# PET_1541_Ada.net
KiCad netlist of a schematic drawn in EAGLE
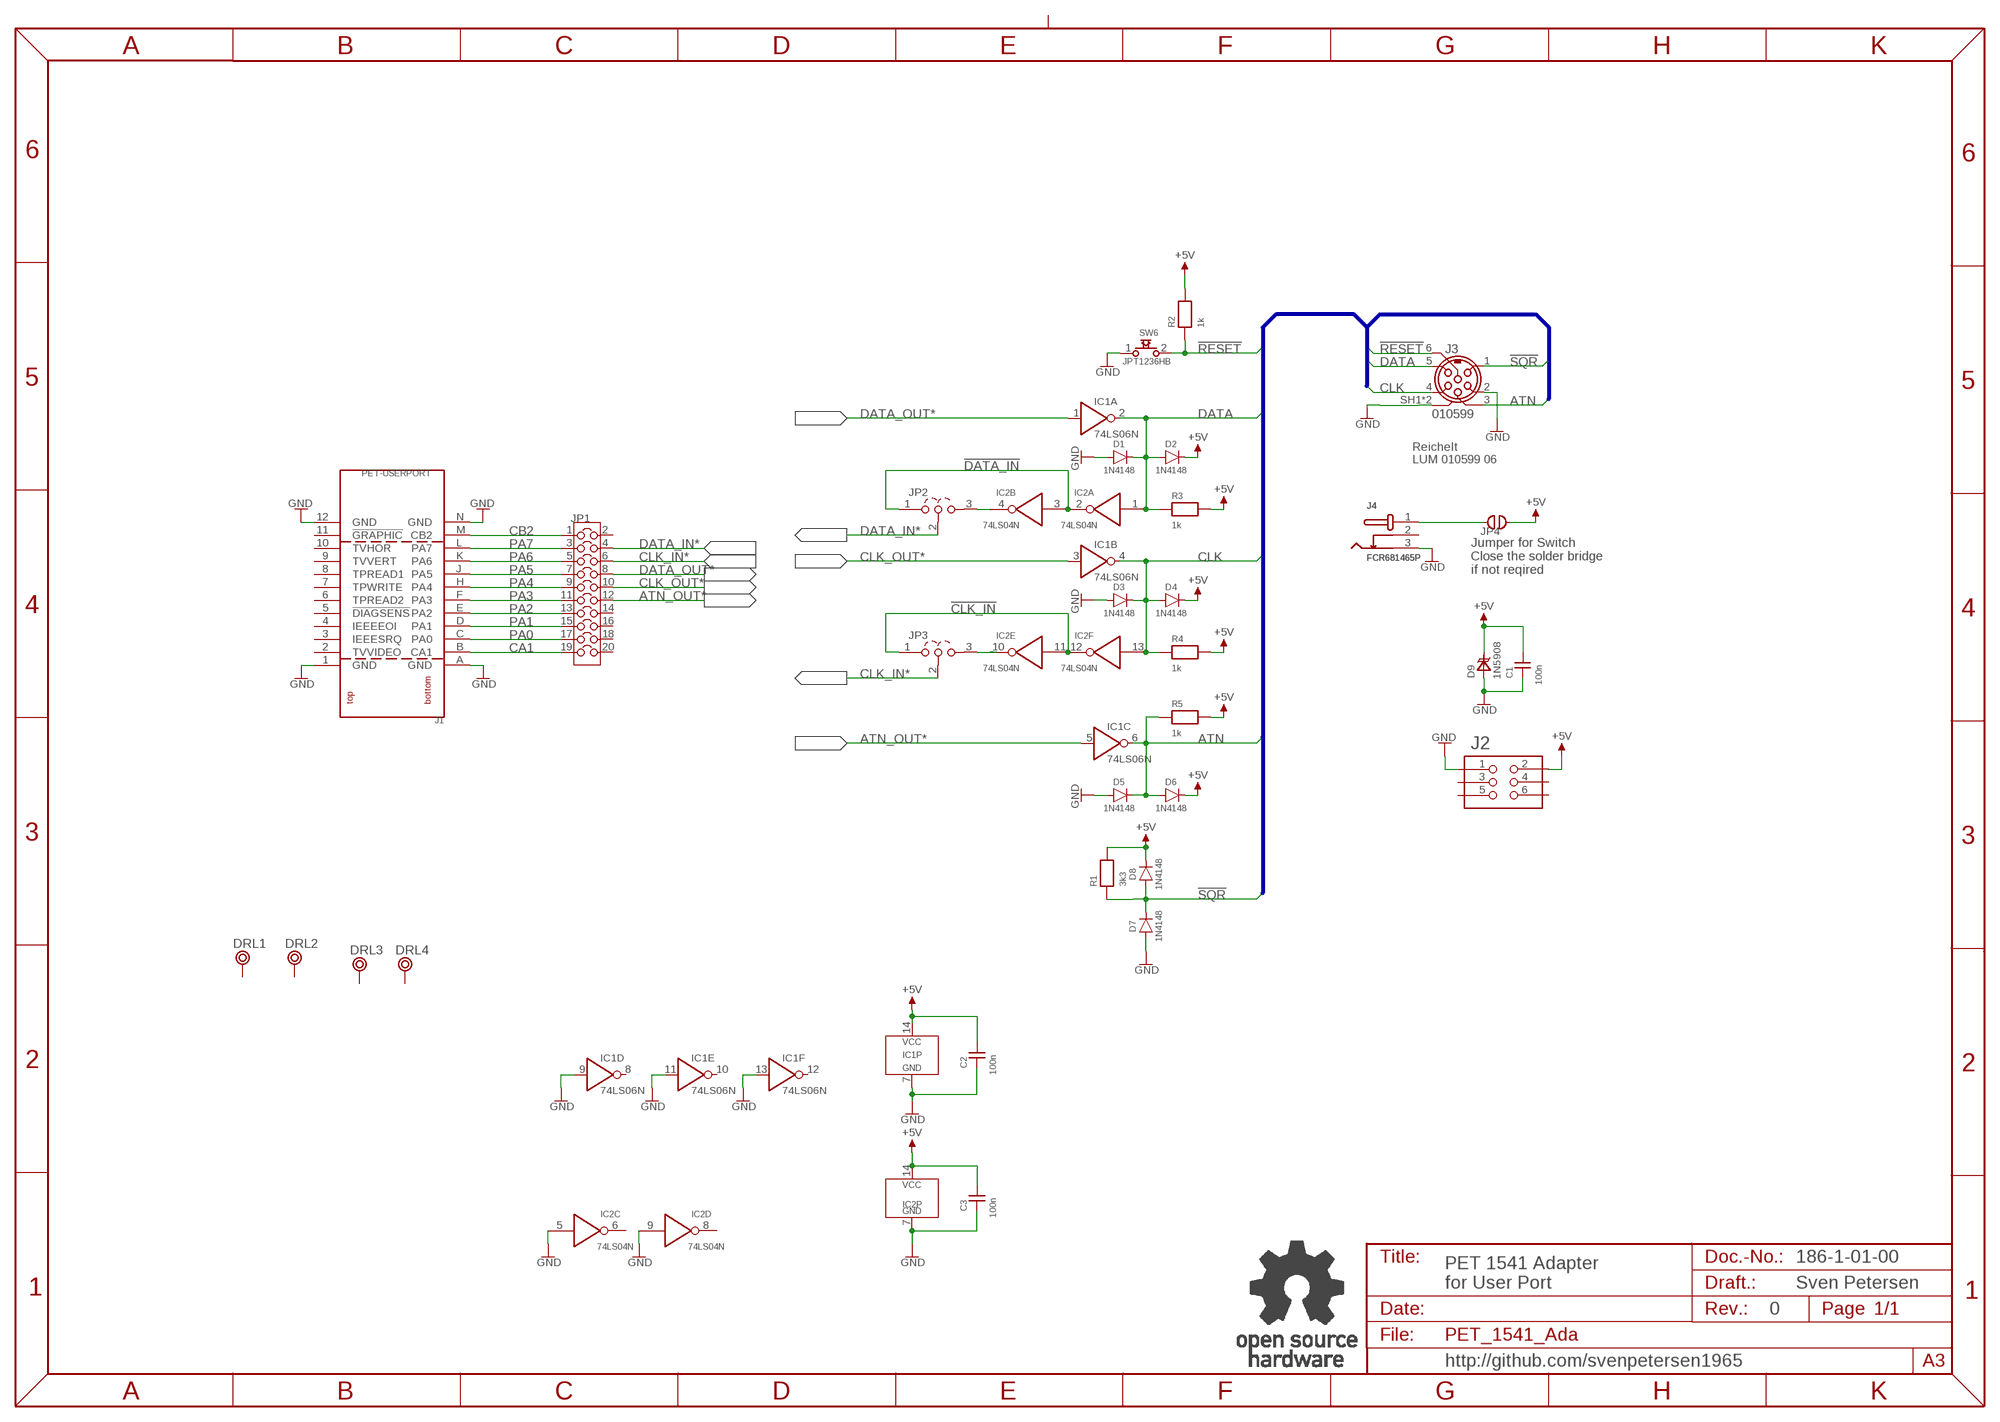
[diagram p0: schematic, sheet 1]

(export (version "E")
  (design (tool "Eeschema 10.0.6"))
  (components
    (comp (ref "C1")
      (value "100n")
      (footprint "eagle-import:C-2,5")
      (libsource (lib "eagle-import") (part "CAP01"))
    )
    (comp (ref "C2")
      (value "100n")
      (footprint "eagle-import:C-2,5")
      (libsource (lib "eagle-import") (part "CAP01"))
    )
    (comp (ref "C3")
      (value "100n")
      (footprint "eagle-import:C-2,5")
      (libsource (lib "eagle-import") (part "CAP01"))
    )
    (comp (ref "D1")
      (value "1N4148")
      (footprint "eagle-import:DO-35_3")
      (libsource (lib "eagle-import") (part "1N41480.3{dblquote}"))
    )
    (comp (ref "D2")
      (value "1N4148")
      (footprint "eagle-import:DO-35_3")
      (libsource (lib "eagle-import") (part "1N41480.3{dblquote}"))
    )
    (comp (ref "D3")
      (value "1N4148")
      (footprint "eagle-import:DO-35_3")
      (libsource (lib "eagle-import") (part "1N41480.3{dblquote}"))
    )
    (comp (ref "D4")
      (value "1N4148")
      (footprint "eagle-import:DO-35_3")
      (libsource (lib "eagle-import") (part "1N41480.3{dblquote}"))
    )
    (comp (ref "D5")
      (value "1N4148")
      (footprint "eagle-import:DO-35_3")
      (libsource (lib "eagle-import") (part "1N41480.3{dblquote}"))
    )
    (comp (ref "D6")
      (value "1N4148")
      (footprint "eagle-import:DO-35_3")
      (libsource (lib "eagle-import") (part "1N41480.3{dblquote}"))
    )
    (comp (ref "D7")
      (value "1N4148")
      (footprint "eagle-import:DO-35_3")
      (libsource (lib "eagle-import") (part "1N41480.3{dblquote}"))
    )
    (comp (ref "D8")
      (value "1N4148")
      (footprint "eagle-import:DO-35_3")
      (libsource (lib "eagle-import") (part "1N41480.3{dblquote}"))
    )
    (comp (ref "D9")
      (value "1N5908")
      (footprint "eagle-import:CB429")
      (libsource (lib "eagle-import") (part "1N5908"))
    )
    (comp (ref "DRL1")
      (value "BOHR3,5")
      (footprint "eagle-import:BOHR3,5")
      (libsource (lib "eagle-import") (part "BOHR3,5"))
    )
    (comp (ref "DRL2")
      (value "BOHR3,5")
      (footprint "eagle-import:BOHR3,5")
      (libsource (lib "eagle-import") (part "BOHR3,5"))
    )
    (comp (ref "DRL3")
      (value "BOHR3,5")
      (footprint "eagle-import:BOHR3,5")
      (libsource (lib "eagle-import") (part "BOHR3,5"))
    )
    (comp (ref "DRL4")
      (value "BOHR3,5")
      (footprint "eagle-import:BOHR3,5")
      (libsource (lib "eagle-import") (part "BOHR3,5"))
    )
    (comp (ref "IC1")
      (value "74LS06N")
      (footprint "eagle-import:DIL-14")
      (libsource (lib "eagle-import") (part "7406N"))
    )
    (comp (ref "IC2")
      (value "74LS04N")
      (footprint "eagle-import:DIL-14")
      (libsource (lib "eagle-import") (part "7404DIL"))
    )
    (comp (ref "J1")
      (value "PET-USERPORT")
      (footprint "eagle-import:USERPORT")
      (libsource (lib "eagle-import") (part "PET-USERPORT"))
    )
    (comp (ref "J2")
      (value "2X03WV")
      (footprint "eagle-import:2X03WV")
      (libsource (lib "eagle-import") (part "2X03WV"))
    )
    (comp (ref "J3")
      (value "010599")
      (footprint "eagle-import:010599")
      (libsource (lib "eagle-import") (part "010599"))
    )
    (comp (ref "J4")
      (value "FCR681465P")
      (footprint "eagle-import:FCR681465P")
      (libsource (lib "eagle-import") (part "FCR681465P"))
    )
    (comp (ref "JP1")
      (value "COMBI_2X10")
      (footprint "eagle-import:COMBI-10X2")
      (libsource (lib "eagle-import") (part "COMBI_2X10"))
    )
    (comp (ref "JP2")
      (value "COMBI-3P")
      (footprint "eagle-import:COMBI-3P")
      (libsource (lib "eagle-import") (part "COMBI-3P"))
    )
    (comp (ref "JP3")
      (value "COMBI-3P")
      (footprint "eagle-import:COMBI-3P")
      (libsource (lib "eagle-import") (part "COMBI-3P"))
    )
    (comp (ref "JP4")
      (value "COMBI_2P")
      (footprint "eagle-import:COMBI-2P")
      (libsource (lib "eagle-import") (part "COMBI_2P"))
    )
    (comp (ref "R1")
      (value "3k3")
      (footprint "eagle-import:R-10")
      (libsource (lib "eagle-import") (part "RES04"))
    )
    (comp (ref "R2")
      (value "1k")
      (footprint "eagle-import:R-10")
      (libsource (lib "eagle-import") (part "RES04"))
    )
    (comp (ref "R3")
      (value "1k")
      (footprint "eagle-import:R-10")
      (libsource (lib "eagle-import") (part "RES04"))
    )
    (comp (ref "R4")
      (value "1k")
      (footprint "eagle-import:R-10")
      (libsource (lib "eagle-import") (part "RES04"))
    )
    (comp (ref "R5")
      (value "1k")
      (footprint "eagle-import:R-10")
      (libsource (lib "eagle-import") (part "RES04"))
    )
    (comp (ref "SW6")
      (value "JPT1236HB")
      (footprint "eagle-import:JTP_1236HB")
      (libsource (lib "eagle-import") (part "JPT1236HB"))
    )
    (comp (ref "U$2")
      (value "OPEN_SOURCE_HW")
      (footprint "eagle-import:OPENHW")
      (libsource (lib "eagle-import") (part "OPEN_SOURCE_HW"))
    )
  )
  (nets
    (net (code "1") (name "+5V") (class "Default")
      (node (ref "C1") (pin "2") (pinfunction "2_2") (pintype "passive"))
      (node (ref "C2") (pin "2") (pinfunction "2_2") (pintype "passive"))
      (node (ref "C3") (pin "2") (pinfunction "2_2") (pintype "passive"))
      (node (ref "D2") (pin "K") (pinfunction "K_K") (pintype "passive"))
      (node (ref "D4") (pin "K") (pinfunction "K_K") (pintype "passive"))
      (node (ref "D6") (pin "K") (pinfunction "K_K") (pintype "passive"))
      (node (ref "D8") (pin "K") (pinfunction "K_K") (pintype "passive"))
      (node (ref "D9") (pin "K") (pinfunction "K_K") (pintype "passive"))
      (node (ref "IC1") (pin "14") (pinfunction "VCC_14") (pintype "bidirectional"))
      (node (ref "IC2") (pin "14") (pinfunction "VCC_14") (pintype "bidirectional"))
      (node (ref "J2") (pin "2") (pinfunction "2_2") (pintype "passive"))
      (node (ref "JP4") (pin "2") (pinfunction "2_2") (pintype "passive"))
      (node (ref "R1") (pin "2") (pinfunction "2_2") (pintype "passive"))
      (node (ref "R2") (pin "2") (pinfunction "2_2") (pintype "passive"))
      (node (ref "R3") (pin "2") (pinfunction "2_2") (pintype "passive"))
      (node (ref "R4") (pin "2") (pinfunction "2_2") (pintype "passive"))
      (node (ref "R5") (pin "2") (pinfunction "2_2") (pintype "passive"))
    )
    (net (code "2") (name "/ATN") (class "Default")
      (node (ref "D5") (pin "K") (pinfunction "K_K") (pintype "passive"))
      (node (ref "D6") (pin "A") (pinfunction "A_A") (pintype "passive"))
      (node (ref "IC1") (pin "6") (pinfunction "O_6") (pintype "open_collector"))
      (node (ref "J3") (pin "3") (pinfunction "3_3") (pintype "bidirectional"))
      (node (ref "R5") (pin "1") (pinfunction "1_1") (pintype "passive"))
    )
    (net (code "3") (name "/ATN_OUT*") (class "Default")
      (node (ref "IC1") (pin "5") (pinfunction "I_5") (pintype "input"))
      (node (ref "JP1") (pin "12") (pinfunction "12_12") (pintype "bidirectional"))
    )
    (net (code "4") (name "/CA1") (class "Default")
      (node (ref "J1") (pin "B") (pinfunction "CA1_B") (pintype "input"))
      (node (ref "JP1") (pin "19") (pinfunction "19_19") (pintype "bidirectional"))
    )
    (net (code "5") (name "/CB2") (class "Default")
      (node (ref "J1") (pin "M") (pinfunction "CB2_M") (pintype "bidirectional"))
      (node (ref "JP1") (pin "1") (pinfunction "1_1") (pintype "bidirectional"))
    )
    (net (code "6") (name "/CLK") (class "Default")
      (node (ref "D3") (pin "K") (pinfunction "K_K") (pintype "passive"))
      (node (ref "D4") (pin "A") (pinfunction "A_A") (pintype "passive"))
      (node (ref "IC1") (pin "4") (pinfunction "O_4") (pintype "open_collector"))
      (node (ref "IC2") (pin "13") (pinfunction "I_13") (pintype "input"))
      (node (ref "J3") (pin "4") (pinfunction "4_4") (pintype "bidirectional"))
      (node (ref "R4") (pin "1") (pinfunction "1_1") (pintype "passive"))
    )
    (net (code "7") (name "/CLK_IN*") (class "Default")
      (node (ref "JP1") (pin "6") (pinfunction "6_6") (pintype "bidirectional"))
      (node (ref "JP3") (pin "2") (pinfunction "2_2") (pintype "bidirectional"))
    )
    (net (code "8") (name "/CLK_OUT*") (class "Default")
      (node (ref "IC1") (pin "3") (pinfunction "I_3") (pintype "input"))
      (node (ref "JP1") (pin "10") (pinfunction "10_10") (pintype "bidirectional"))
    )
    (net (code "9") (name "/DATA") (class "Default")
      (node (ref "D1") (pin "K") (pinfunction "K_K") (pintype "passive"))
      (node (ref "D2") (pin "A") (pinfunction "A_A") (pintype "passive"))
      (node (ref "IC1") (pin "2") (pinfunction "O_2") (pintype "open_collector"))
      (node (ref "IC2") (pin "1") (pinfunction "I_1") (pintype "input"))
      (node (ref "J3") (pin "5") (pinfunction "5_5") (pintype "bidirectional"))
      (node (ref "R3") (pin "1") (pinfunction "1_1") (pintype "passive"))
    )
    (net (code "10") (name "/DATA_IN*") (class "Default")
      (node (ref "JP1") (pin "4") (pinfunction "4_4") (pintype "bidirectional"))
      (node (ref "JP2") (pin "2") (pinfunction "2_2") (pintype "bidirectional"))
    )
    (net (code "11") (name "/DATA_OUT*") (class "Default")
      (node (ref "IC1") (pin "1") (pinfunction "I_1") (pintype "input"))
      (node (ref "JP1") (pin "8") (pinfunction "8_8") (pintype "bidirectional"))
    )
    (net (code "12") (name "/PA0") (class "Default")
      (node (ref "J1") (pin "C") (pinfunction "PA0_C") (pintype "bidirectional"))
      (node (ref "JP1") (pin "17") (pinfunction "17_17") (pintype "bidirectional"))
    )
    (net (code "13") (name "/PA1") (class "Default")
      (node (ref "J1") (pin "D") (pinfunction "PA1_D") (pintype "bidirectional"))
      (node (ref "JP1") (pin "15") (pinfunction "15_15") (pintype "bidirectional"))
    )
    (net (code "14") (name "/PA2") (class "Default")
      (node (ref "J1") (pin "E") (pinfunction "PA2_E") (pintype "bidirectional"))
      (node (ref "JP1") (pin "13") (pinfunction "13_13") (pintype "bidirectional"))
    )
    (net (code "15") (name "/PA3") (class "Default")
      (node (ref "J1") (pin "F") (pinfunction "PA3_F") (pintype "bidirectional"))
      (node (ref "JP1") (pin "11") (pinfunction "11_11") (pintype "bidirectional"))
    )
    (net (code "16") (name "/PA4") (class "Default")
      (node (ref "J1") (pin "H") (pinfunction "PA4_H") (pintype "bidirectional"))
      (node (ref "JP1") (pin "9") (pinfunction "9_9") (pintype "bidirectional"))
    )
    (net (code "17") (name "/PA5") (class "Default")
      (node (ref "J1") (pin "J") (pinfunction "PA5_J") (pintype "bidirectional"))
      (node (ref "JP1") (pin "7") (pinfunction "7_7") (pintype "bidirectional"))
    )
    (net (code "18") (name "/PA6") (class "Default")
      (node (ref "J1") (pin "K") (pinfunction "PA6_K") (pintype "bidirectional"))
      (node (ref "JP1") (pin "5") (pinfunction "5_5") (pintype "bidirectional"))
    )
    (net (code "19") (name "/PA7") (class "Default")
      (node (ref "J1") (pin "L") (pinfunction "PA7_L") (pintype "bidirectional"))
      (node (ref "JP1") (pin "3") (pinfunction "3_3") (pintype "bidirectional"))
    )
    (net (code "20") (name "/~{CLK_IN}") (class "Default")
      (node (ref "IC2") (pin "11") (pinfunction "I_11") (pintype "input"))
      (node (ref "IC2") (pin "12") (pinfunction "O_12") (pintype "output"))
      (node (ref "JP3") (pin "1") (pinfunction "1_1") (pintype "bidirectional"))
    )
    (net (code "21") (name "/~{DATA_IN}") (class "Default")
      (node (ref "IC2") (pin "2") (pinfunction "O_2") (pintype "output"))
      (node (ref "IC2") (pin "3") (pinfunction "I_3") (pintype "input"))
      (node (ref "JP2") (pin "1") (pinfunction "1_1") (pintype "bidirectional"))
    )
    (net (code "22") (name "/~{RESET}") (class "Default")
      (node (ref "J3") (pin "6") (pinfunction "6_6") (pintype "bidirectional"))
      (node (ref "R2") (pin "1") (pinfunction "1_1") (pintype "passive"))
      (node (ref "SW6") (pin "2") (pinfunction "2_2") (pintype "passive"))
    )
    (net (code "23") (name "/~{SQR}") (class "Default")
      (node (ref "D7") (pin "K") (pinfunction "K_K") (pintype "passive"))
      (node (ref "D8") (pin "A") (pinfunction "A_A") (pintype "passive"))
      (node (ref "J3") (pin "1") (pinfunction "1_1") (pintype "bidirectional"))
      (node (ref "R1") (pin "1") (pinfunction "1_1") (pintype "passive"))
    )
    (net (code "24") (name "GND") (class "Default")
      (node (ref "C1") (pin "1") (pinfunction "1_1") (pintype "passive"))
      (node (ref "C2") (pin "1") (pinfunction "1_1") (pintype "passive"))
      (node (ref "C3") (pin "1") (pinfunction "1_1") (pintype "passive"))
      (node (ref "D1") (pin "A") (pinfunction "A_A") (pintype "passive"))
      (node (ref "D3") (pin "A") (pinfunction "A_A") (pintype "passive"))
      (node (ref "D5") (pin "A") (pinfunction "A_A") (pintype "passive"))
      (node (ref "D7") (pin "A") (pinfunction "A_A") (pintype "passive"))
      (node (ref "D9") (pin "A") (pinfunction "A_A") (pintype "passive"))
      (node (ref "IC1") (pin "11") (pinfunction "I_11") (pintype "input"))
      (node (ref "IC1") (pin "13") (pinfunction "I_13") (pintype "input"))
      (node (ref "IC1") (pin "7") (pinfunction "GND_7") (pintype "bidirectional"))
      (node (ref "IC1") (pin "9") (pinfunction "I_9") (pintype "input"))
      (node (ref "IC2") (pin "5") (pinfunction "I_5") (pintype "input"))
      (node (ref "IC2") (pin "7") (pinfunction "GND_7") (pintype "bidirectional"))
      (node (ref "IC2") (pin "9") (pinfunction "I_9") (pintype "input"))
      (node (ref "J1") (pin "1") (pinfunction "GND_1") (pintype "power_in"))
      (node (ref "J1") (pin "12") (pinfunction "GND_12") (pintype "power_in"))
      (node (ref "J1") (pin "A") (pinfunction "GND_A") (pintype "power_in"))
      (node (ref "J1") (pin "N") (pinfunction "GND_N") (pintype "power_in"))
      (node (ref "J2") (pin "1") (pinfunction "1_1") (pintype "passive"))
      (node (ref "J3") (pin "2") (pinfunction "2_2") (pintype "bidirectional"))
      (node (ref "J3") (pin "SH1") (pinfunction "SH_SH1") (pintype "bidirectional"))
      (node (ref "J3") (pin "SH2") (pinfunction "SH_SH2") (pintype "bidirectional"))
      (node (ref "J4") (pin "3") (pinfunction "3_3") (pintype "bidirectional"))
      (node (ref "SW6") (pin "1") (pinfunction "1_1") (pintype "passive"))
    )
    (net (code "25") (name "Net-(IC2B-O)") (class "Default")
      (node (ref "IC2") (pin "4") (pinfunction "O_4") (pintype "output"))
      (node (ref "JP2") (pin "3") (pinfunction "3_3") (pintype "bidirectional"))
    )
    (net (code "26") (name "Net-(IC2E-O)") (class "Default")
      (node (ref "IC2") (pin "10") (pinfunction "O_10") (pintype "output"))
      (node (ref "JP3") (pin "3") (pinfunction "3_3") (pintype "bidirectional"))
    )
    (net (code "27") (name "Net-(J4-Pad1)") (class "Default")
      (node (ref "J4") (pin "1") (pinfunction "1_1") (pintype "bidirectional"))
      (node (ref "JP4") (pin "1") (pinfunction "1_1") (pintype "passive"))
    )
    (net (code "28") (name "unconnected-(DRL1-PadP$1)") (class "Default")
      (node (ref "DRL1") (pin "P$1") (pinfunction "P$1_P$1") (pintype "passive"))
    )
    (net (code "29") (name "unconnected-(DRL2-PadP$1)") (class "Default")
      (node (ref "DRL2") (pin "P$1") (pinfunction "P$1_P$1") (pintype "passive"))
    )
    (net (code "30") (name "unconnected-(DRL3-PadP$1)") (class "Default")
      (node (ref "DRL3") (pin "P$1") (pinfunction "P$1_P$1") (pintype "passive"))
    )
    (net (code "31") (name "unconnected-(DRL4-PadP$1)") (class "Default")
      (node (ref "DRL4") (pin "P$1") (pinfunction "P$1_P$1") (pintype "passive"))
    )
    (net (code "32") (name "unconnected-(IC1D-O-Pad8)") (class "Default")
      (node (ref "IC1") (pin "8") (pinfunction "O_8") (pintype "open_collector"))
    )
    (net (code "33") (name "unconnected-(IC1E-O-Pad10)") (class "Default")
      (node (ref "IC1") (pin "10") (pinfunction "O_10") (pintype "open_collector"))
    )
    (net (code "34") (name "unconnected-(IC1F-O-Pad12)") (class "Default")
      (node (ref "IC1") (pin "12") (pinfunction "O_12") (pintype "open_collector"))
    )
    (net (code "35") (name "unconnected-(IC2C-O-Pad6)") (class "Default")
      (node (ref "IC2") (pin "6") (pinfunction "O_6") (pintype "output"))
    )
    (net (code "36") (name "unconnected-(IC2D-O-Pad8)") (class "Default")
      (node (ref "IC2") (pin "8") (pinfunction "O_8") (pintype "output"))
    )
    (net (code "37") (name "unconnected-(J1-IEEEEOI-Pad4)") (class "Default")
      (node (ref "J1") (pin "4") (pinfunction "IEEEEOI_4") (pintype "output"))
    )
    (net (code "38") (name "unconnected-(J1-IEEESRQ-Pad3)") (class "Default")
      (node (ref "J1") (pin "3") (pinfunction "IEEESRQ_3") (pintype "output"))
    )
    (net (code "39") (name "unconnected-(J1-TPREAD1-Pad8)") (class "Default")
      (node (ref "J1") (pin "8") (pinfunction "TPREAD1_8") (pintype "output"))
    )
    (net (code "40") (name "unconnected-(J1-TPREAD2-Pad6)") (class "Default")
      (node (ref "J1") (pin "6") (pinfunction "TPREAD2_6") (pintype "output"))
    )
    (net (code "41") (name "unconnected-(J1-TPWRITE-Pad7)") (class "Default")
      (node (ref "J1") (pin "7") (pinfunction "TPWRITE_7") (pintype "output"))
    )
    (net (code "42") (name "unconnected-(J1-TVHOR-Pad10)") (class "Default")
      (node (ref "J1") (pin "10") (pinfunction "TVHOR_10") (pintype "output"))
    )
    (net (code "43") (name "unconnected-(J1-TVVERT-Pad9)") (class "Default")
      (node (ref "J1") (pin "9") (pinfunction "TVVERT_9") (pintype "output"))
    )
    (net (code "44") (name "unconnected-(J1-TVVIDEO-Pad2)") (class "Default")
      (node (ref "J1") (pin "2") (pinfunction "TVVIDEO_2") (pintype "output"))
    )
    (net (code "45") (name "unconnected-(J1-~{DIAGSENS}-Pad5)") (class "Default")
      (node (ref "J1") (pin "5") (pinfunction "~{DIAGSENS}_5") (pintype "output"))
    )
    (net (code "46") (name "unconnected-(J1-~{GRAPHIC}-Pad11)") (class "Default")
      (node (ref "J1") (pin "11") (pinfunction "~{GRAPHIC}_11") (pintype "output"))
    )
    (net (code "47") (name "unconnected-(J2-Pad3)") (class "Default")
      (node (ref "J2") (pin "3") (pinfunction "3_3") (pintype "passive"))
    )
    (net (code "48") (name "unconnected-(J2-Pad4)") (class "Default")
      (node (ref "J2") (pin "4") (pinfunction "4_4") (pintype "passive"))
    )
    (net (code "49") (name "unconnected-(J2-Pad5)") (class "Default")
      (node (ref "J2") (pin "5") (pinfunction "5_5") (pintype "passive"))
    )
    (net (code "50") (name "unconnected-(J2-Pad6)") (class "Default")
      (node (ref "J2") (pin "6") (pinfunction "6_6") (pintype "passive"))
    )
    (net (code "51") (name "unconnected-(J4-Pad2)") (class "Default")
      (node (ref "J4") (pin "2") (pinfunction "2_2") (pintype "bidirectional"))
    )
    (net (code "52") (name "unconnected-(JP1-Pad2)") (class "Default")
      (node (ref "JP1") (pin "2") (pinfunction "2_2") (pintype "bidirectional"))
    )
    (net (code "53") (name "unconnected-(JP1-Pad14)") (class "Default")
      (node (ref "JP1") (pin "14") (pinfunction "14_14") (pintype "bidirectional"))
    )
    (net (code "54") (name "unconnected-(JP1-Pad16)") (class "Default")
      (node (ref "JP1") (pin "16") (pinfunction "16_16") (pintype "bidirectional"))
    )
    (net (code "55") (name "unconnected-(JP1-Pad18)") (class "Default")
      (node (ref "JP1") (pin "18") (pinfunction "18_18") (pintype "bidirectional"))
    )
    (net (code "56") (name "unconnected-(JP1-Pad20)") (class "Default")
      (node (ref "JP1") (pin "20") (pinfunction "20_20") (pintype "bidirectional"))
    )
  )
)
